# metiumacs.net
KiCad netlist of a schematic drawn in EAGLE
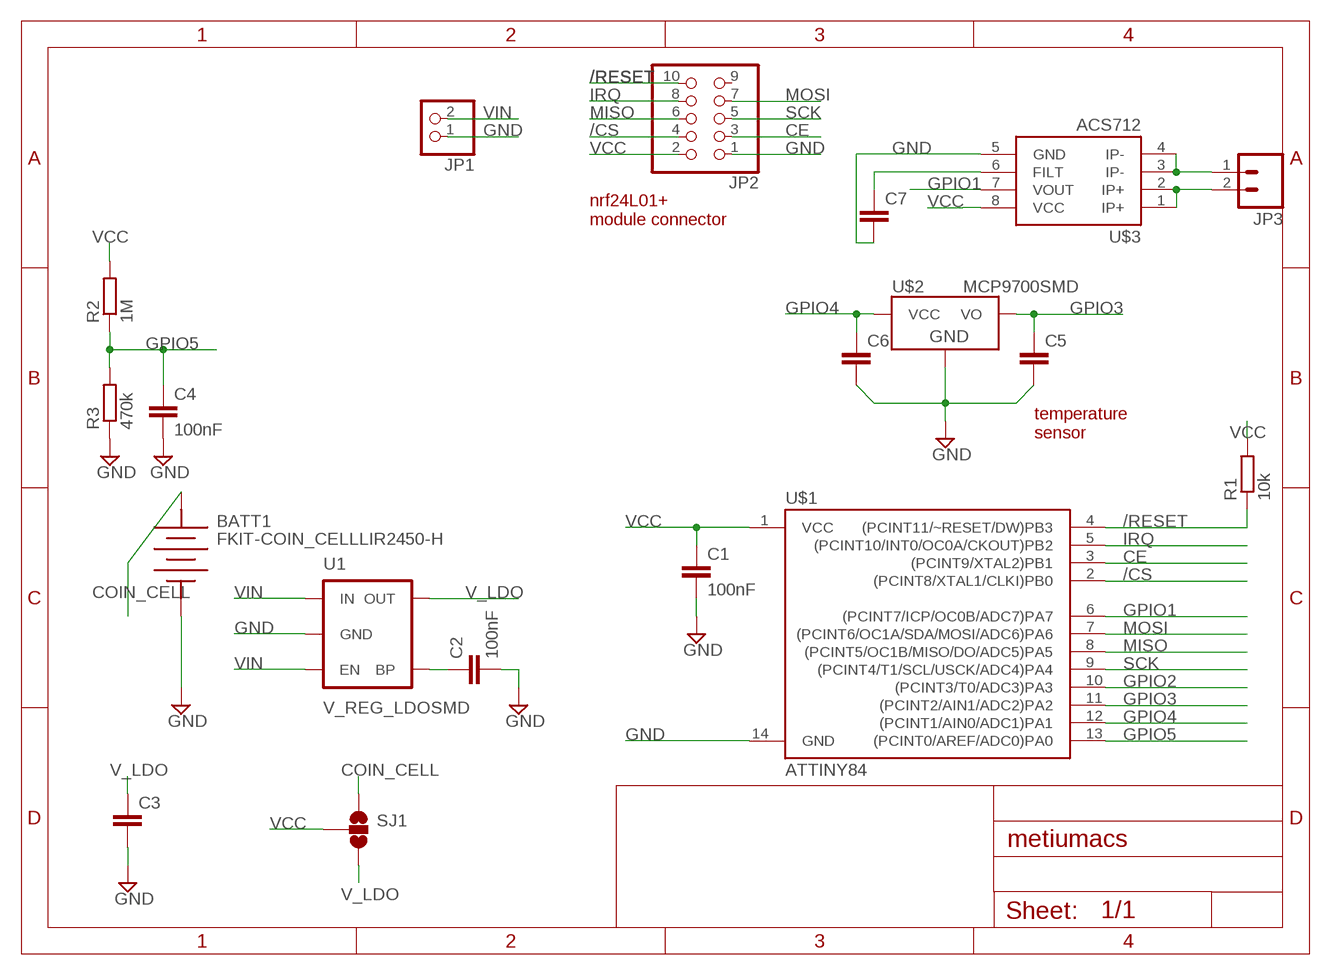
[diagram p0: schematic, sheet 1]

(export (version "E")
  (design (tool "Eeschema 10.0.6"))
  (components
    (comp (ref "BATT1")
      (value "FKIT-COIN_CELLLIR2450-H")
      (footprint "eagle-import:FKIT-LIR2450-H")
      (libsource (lib "eagle-import") (part "FKIT-COIN_CELLLIR2450-H"))
    )
    (comp (ref "C1")
      (value "100nF")
      (footprint "eagle-import:C0805")
      (libsource (lib "eagle-import") (part "C-EUC0805"))
    )
    (comp (ref "C2")
      (value "100nF")
      (footprint "eagle-import:C0805")
      (libsource (lib "eagle-import") (part "C-EUC0805"))
    )
    (comp (ref "C3")
      (value "C-EUC0805")
      (footprint "eagle-import:C0805")
      (libsource (lib "eagle-import") (part "C-EUC0805"))
    )
    (comp (ref "C4")
      (value "100nF")
      (footprint "eagle-import:C0805")
      (libsource (lib "eagle-import") (part "C-EUC0805"))
    )
    (comp (ref "C5")
      (value "C-EUC0805")
      (footprint "eagle-import:C0805")
      (libsource (lib "eagle-import") (part "C-EUC0805"))
    )
    (comp (ref "C6")
      (value "C-EUC0805")
      (footprint "eagle-import:C0805")
      (libsource (lib "eagle-import") (part "C-EUC0805"))
    )
    (comp (ref "C7")
      (value "CAP0805")
      (footprint "eagle-import:0805")
      (libsource (lib "eagle-import") (part "CAP0805"))
    )
    (comp (ref "JP1")
      (value "HEADER-1X2ROUND")
      (footprint "eagle-import:1X02_ROUND")
      (libsource (lib "eagle-import") (part "HEADER-1X2ROUND"))
    )
    (comp (ref "JP2")
      (value "PINHD-2X5")
      (footprint "eagle-import:2X05")
      (libsource (lib "eagle-import") (part "PINHD-2X5"))
    )
    (comp (ref "JP3")
      (value "M02PTH4")
      (footprint "eagle-import:1X02_XTRA_BIG")
      (libsource (lib "eagle-import") (part "M02PTH4"))
    )
    (comp (ref "R1")
      (value "10k")
      (footprint "eagle-import:R0805")
      (libsource (lib "eagle-import") (part "R-EU_R0805"))
    )
    (comp (ref "R2")
      (value "1M")
      (footprint "eagle-import:R0805")
      (libsource (lib "eagle-import") (part "R-EU_R0805"))
    )
    (comp (ref "R3")
      (value "470k")
      (footprint "eagle-import:R0805")
      (libsource (lib "eagle-import") (part "R-EU_R0805"))
    )
    (comp (ref "SJ1")
      (value "SOLDERJUMPER_2WAYS")
      (footprint "eagle-import:SJ_3")
      (libsource (lib "eagle-import") (part "SOLDERJUMPER_2WAYS"))
    )
    (comp (ref "U$1")
      (value "ATTINY84")
      (footprint "eagle-import:SO14")
      (libsource (lib "eagle-import") (part "ATTINY84"))
    )
    (comp (ref "U$2")
      (value "MCP9700SMD")
      (footprint "eagle-import:SOT23-3")
      (libsource (lib "eagle-import") (part "MCP9700SMD"))
    )
    (comp (ref "U$3")
      (value "ACS712")
      (footprint "eagle-import:SO08")
      (libsource (lib "eagle-import") (part "ACS712"))
    )
    (comp (ref "U1")
      (value "V_REG_LDOSMD")
      (footprint "eagle-import:SOT23-5")
      (libsource (lib "eagle-import") (part "V_REG_LDOSMD"))
    )
  )
  (nets
    (net (code "1") (name "/CE") (class "Default")
      (node (ref "JP2") (pin "3") (pinfunction "3_3") (pintype "passive"))
      (node (ref "U$1") (pin "3") (pinfunction "(PCINT9/XTAL2)PB1_3") (pintype "bidirectional"))
    )
    (net (code "2") (name "/COIN_CELL") (class "Default")
      (node (ref "BATT1") (pin "POS") (pinfunction "POS_POS") (pintype "bidirectional"))
      (node (ref "SJ1") (pin "1") (pinfunction "1_1") (pintype "passive"))
    )
    (net (code "3") (name "/GPIO1") (class "Default")
      (node (ref "U$1") (pin "6") (pinfunction "(PCINT7/ICP/OC0B/ADC7)PA7_6") (pintype "bidirectional"))
      (node (ref "U$3") (pin "7") (pinfunction "VOUT_7") (pintype "bidirectional"))
    )
    (net (code "4") (name "/GPIO2") (class "Default")
      (node (ref "U$1") (pin "10") (pinfunction "(PCINT3/T0/ADC3)PA3_10") (pintype "bidirectional"))
    )
    (net (code "5") (name "/GPIO3") (class "Default")
      (node (ref "C5") (pin "1") (pinfunction "1_1") (pintype "passive"))
      (node (ref "U$1") (pin "11") (pinfunction "(PCINT2/AIN1/ADC2)PA2_11") (pintype "bidirectional"))
      (node (ref "U$2") (pin "2") (pinfunction "VO_2") (pintype "bidirectional"))
    )
    (net (code "6") (name "/GPIO4") (class "Default")
      (node (ref "C6") (pin "1") (pinfunction "1_1") (pintype "passive"))
      (node (ref "U$1") (pin "12") (pinfunction "(PCINT1/AIN0/ADC1)PA1_12") (pintype "bidirectional"))
      (node (ref "U$2") (pin "1") (pinfunction "VCC_1") (pintype "bidirectional"))
    )
    (net (code "7") (name "/GPIO5") (class "Default")
      (node (ref "C4") (pin "1") (pinfunction "1_1") (pintype "passive"))
      (node (ref "R2") (pin "1") (pinfunction "1_1") (pintype "passive"))
      (node (ref "R3") (pin "2") (pinfunction "2_2") (pintype "passive"))
      (node (ref "U$1") (pin "13") (pinfunction "(PCINT0/AREF/ADC0)PA0_13") (pintype "bidirectional"))
    )
    (net (code "8") (name "/IRQ") (class "Default")
      (node (ref "JP2") (pin "8") (pinfunction "8_8") (pintype "passive"))
      (node (ref "U$1") (pin "5") (pinfunction "(PCINT10/INT0/OC0A/CKOUT)PB2_5") (pintype "bidirectional"))
    )
    (net (code "9") (name "/MISO") (class "Default")
      (node (ref "JP2") (pin "6") (pinfunction "6_6") (pintype "passive"))
      (node (ref "U$1") (pin "8") (pinfunction "(PCINT5/OC1B/MISO/DO/ADC5)PA5_8") (pintype "bidirectional"))
    )
    (net (code "10") (name "/MOSI") (class "Default")
      (node (ref "JP2") (pin "7") (pinfunction "7_7") (pintype "passive"))
      (node (ref "U$1") (pin "7") (pinfunction "(PCINT6/OC1A/SDA/MOSI/ADC6)PA6_7") (pintype "bidirectional"))
    )
    (net (code "11") (name "/SCK") (class "Default")
      (node (ref "JP2") (pin "5") (pinfunction "5_5") (pintype "passive"))
      (node (ref "U$1") (pin "9") (pinfunction "(PCINT4/T1/SCL/USCK/ADC4)PA4_9") (pintype "bidirectional"))
    )
    (net (code "12") (name "/VCC") (class "Default")
      (node (ref "C1") (pin "1") (pinfunction "1_1") (pintype "passive"))
      (node (ref "JP2") (pin "2") (pinfunction "2_2") (pintype "passive"))
      (node (ref "R1") (pin "2") (pinfunction "2_2") (pintype "passive"))
      (node (ref "R2") (pin "2") (pinfunction "2_2") (pintype "passive"))
      (node (ref "SJ1") (pin "2") (pinfunction "2_2") (pintype "passive"))
      (node (ref "U$1") (pin "1") (pinfunction "VCC_1") (pintype "bidirectional"))
      (node (ref "U$3") (pin "8") (pinfunction "VCC_8") (pintype "bidirectional"))
    )
    (net (code "13") (name "/VIN") (class "Default")
      (node (ref "JP1") (pin "2") (pinfunction "2_2") (pintype "passive"))
      (node (ref "U1") (pin "1") (pinfunction "IN_1") (pintype "input"))
      (node (ref "U1") (pin "3") (pinfunction "EN_3") (pintype "input"))
    )
    (net (code "14") (name "/V_LDO") (class "Default")
      (node (ref "C3") (pin "1") (pinfunction "1_1") (pintype "passive"))
      (node (ref "SJ1") (pin "3") (pinfunction "3_3") (pintype "passive"))
      (node (ref "U1") (pin "5") (pinfunction "OUT_5") (pintype "passive"))
    )
    (net (code "15") (name "/{slash}CS") (class "Default")
      (node (ref "JP2") (pin "4") (pinfunction "4_4") (pintype "passive"))
      (node (ref "U$1") (pin "2") (pinfunction "(PCINT8/XTAL1/CLKI)PB0_2") (pintype "bidirectional"))
    )
    (net (code "16") (name "/{slash}RESET") (class "Default")
      (node (ref "JP2") (pin "10") (pinfunction "10_10") (pintype "passive"))
      (node (ref "R1") (pin "1") (pinfunction "1_1") (pintype "passive"))
      (node (ref "U$1") (pin "4") (pinfunction "(PCINT11/~{RESET/DW})PB3_4") (pintype "bidirectional"))
    )
    (net (code "17") (name "GND") (class "Default")
      (node (ref "BATT1") (pin "NEG") (pinfunction "NEG_NEG") (pintype "bidirectional"))
      (node (ref "C1") (pin "2") (pinfunction "2_2") (pintype "passive"))
      (node (ref "C2") (pin "2") (pinfunction "2_2") (pintype "passive"))
      (node (ref "C3") (pin "2") (pinfunction "2_2") (pintype "passive"))
      (node (ref "C4") (pin "2") (pinfunction "2_2") (pintype "passive"))
      (node (ref "C5") (pin "2") (pinfunction "2_2") (pintype "passive"))
      (node (ref "C6") (pin "2") (pinfunction "2_2") (pintype "passive"))
      (node (ref "C7") (pin "2") (pinfunction "2_2") (pintype "passive"))
      (node (ref "JP1") (pin "1") (pinfunction "1_1") (pintype "passive"))
      (node (ref "JP2") (pin "1") (pinfunction "1_1") (pintype "passive"))
      (node (ref "R3") (pin "1") (pinfunction "1_1") (pintype "passive"))
      (node (ref "U$1") (pin "14") (pinfunction "GND_14") (pintype "bidirectional"))
      (node (ref "U$2") (pin "3") (pinfunction "GND_3") (pintype "bidirectional"))
      (node (ref "U$3") (pin "5") (pinfunction "GND_5") (pintype "bidirectional"))
      (node (ref "U1") (pin "2") (pinfunction "GND_2") (pintype "input"))
    )
    (net (code "18") (name "Net-(JP3-Pad1)") (class "Default")
      (node (ref "JP3") (pin "1") (pinfunction "1_1") (pintype "passive"))
      (node (ref "U$3") (pin "3") (pinfunction "IP-_3") (pintype "bidirectional"))
      (node (ref "U$3") (pin "4") (pinfunction "IP-_4") (pintype "bidirectional"))
    )
    (net (code "19") (name "Net-(JP3-Pad2)") (class "Default")
      (node (ref "JP3") (pin "2") (pinfunction "2_2") (pintype "passive"))
      (node (ref "U$3") (pin "1") (pinfunction "IP+_1") (pintype "bidirectional"))
      (node (ref "U$3") (pin "2") (pinfunction "IP+_2") (pintype "bidirectional"))
    )
    (net (code "20") (name "Net-(U$3-FILT)") (class "Default")
      (node (ref "C7") (pin "1") (pinfunction "1_1") (pintype "passive"))
      (node (ref "U$3") (pin "6") (pinfunction "FILT_6") (pintype "bidirectional"))
    )
    (net (code "21") (name "Net-(U1-BP)") (class "Default")
      (node (ref "C2") (pin "1") (pinfunction "1_1") (pintype "passive"))
      (node (ref "U1") (pin "4") (pinfunction "BP_4") (pintype "input"))
    )
    (net (code "22") (name "unconnected-(JP2-Pad9)") (class "Default")
      (node (ref "JP2") (pin "9") (pinfunction "9_9") (pintype "passive"))
    )
  )
)
